# TCAN1146_PINOUT.net
KiCad netlist of a schematic drawn in Altium Designer
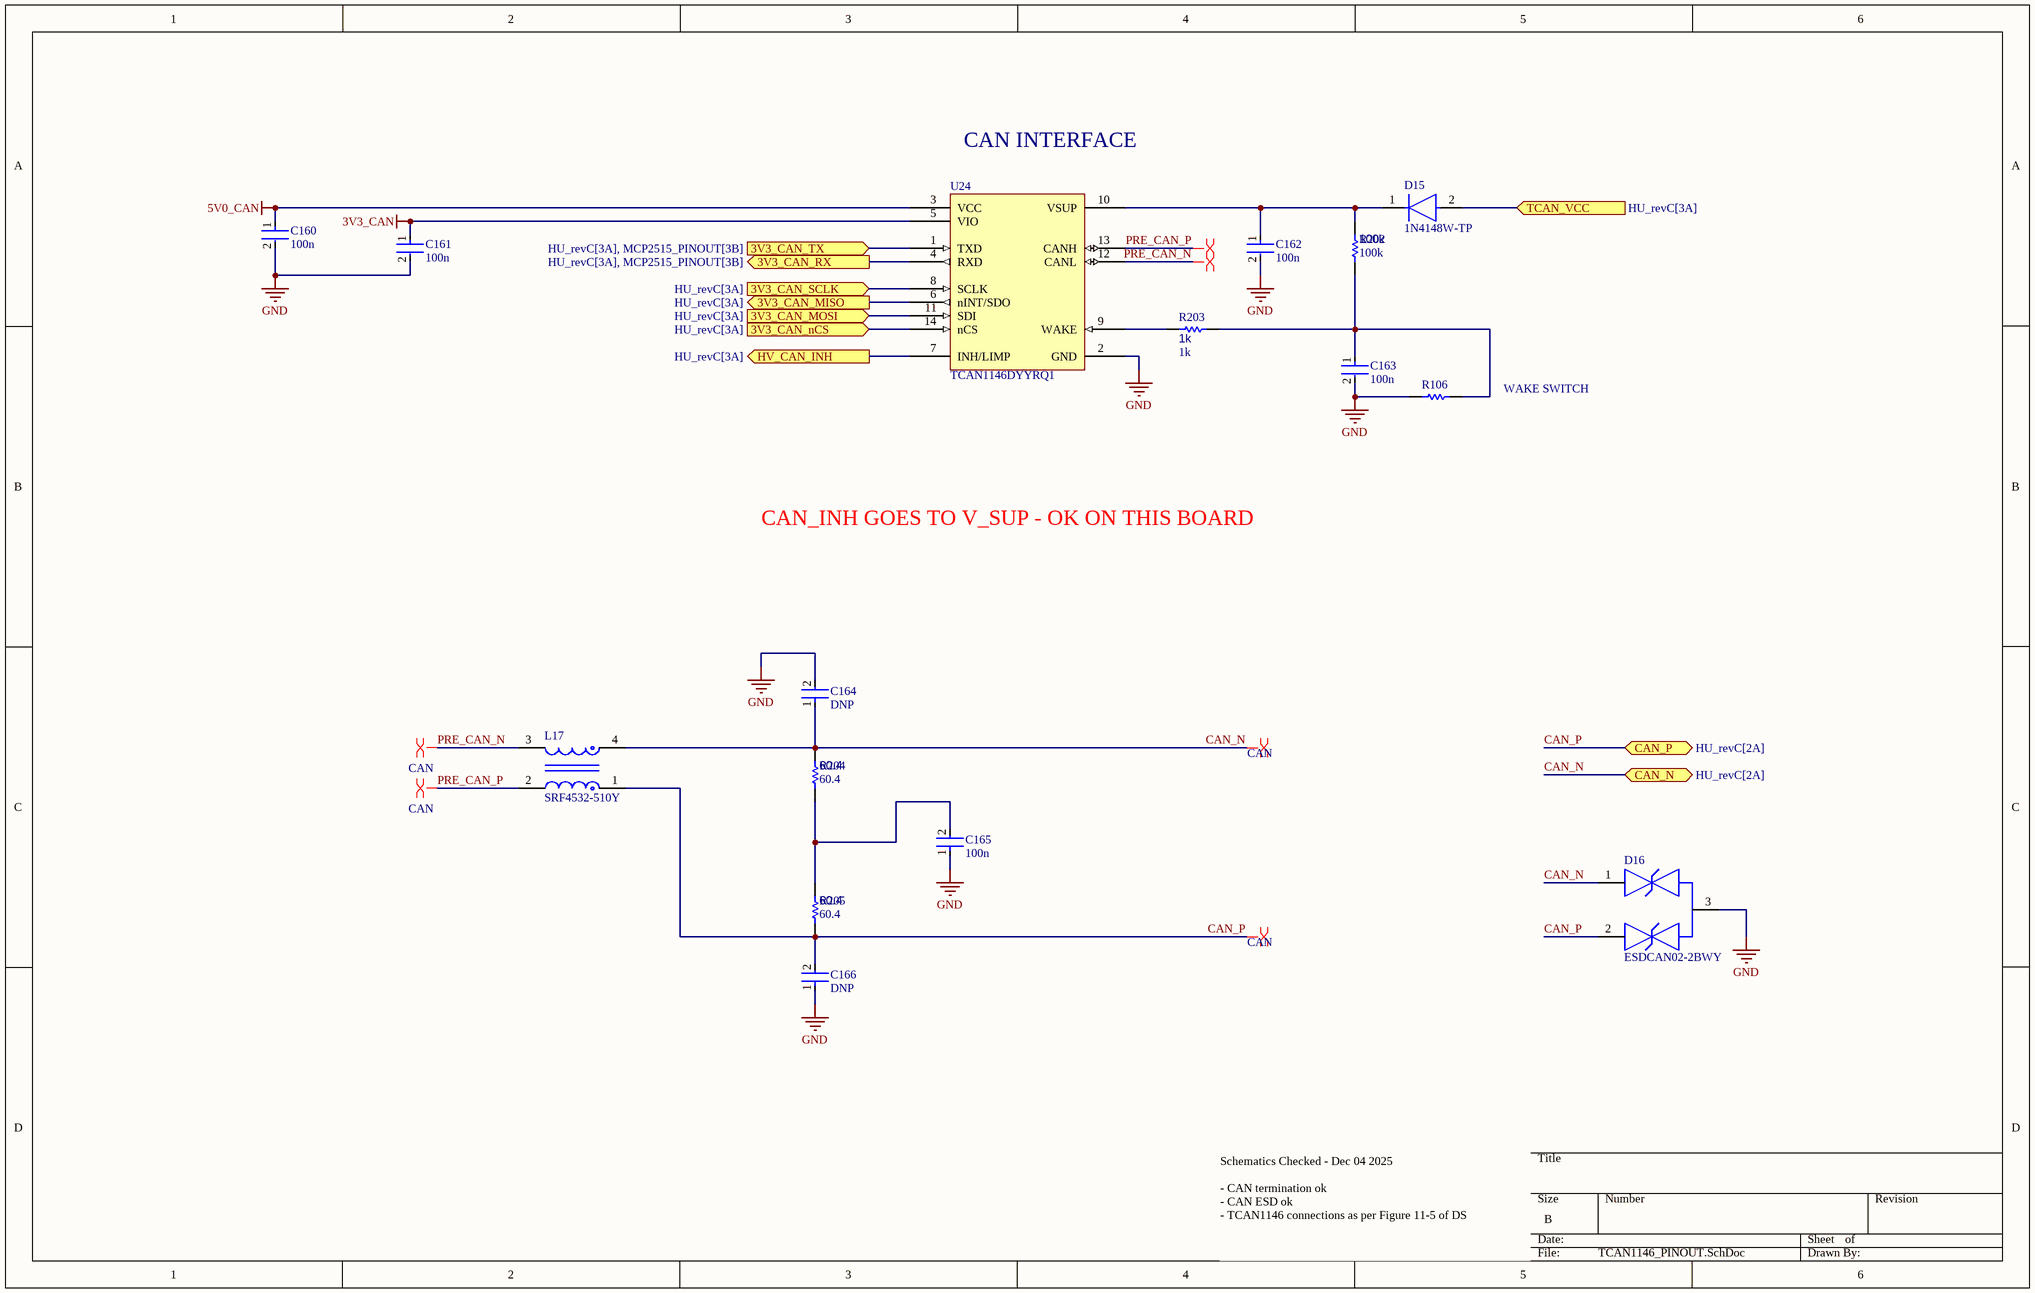
[diagram p0: TCAN1146_PINOUT.SchDoc]

(export (version "E")
  (design (tool "Eeschema 10.0.6"))
  (components
    (comp (ref "C160")
      (value "100n")
      (footprint "FP-0402-L_1_0_0_05-W_0_5-IPC_A")
      (description "LARGE PADS, 0402 CAP, CHANGE COMMENT TO MATCH REAL P/N")
      (libsource (lib "Space Concordia") (part "b4654b650e69147ec39a6b967a45e02"))
    )
    (comp (ref "C161")
      (value "100n")
      (footprint "FP-0402-L_1_0_0_05-W_0_5-IPC_A")
      (description "LARGE PADS, 0402 CAP, CHANGE COMMENT TO MATCH REAL P/N")
      (libsource (lib "Space Concordia") (part "b4654b650e69147ec39a6b967a45e02"))
    )
    (comp (ref "C162")
      (value "100n")
      (footprint "FP-0402-L_1_0_0_05-W_0_5-IPC_A")
      (description "LARGE PADS, 0402 CAP, CHANGE COMMENT TO MATCH REAL P/N")
      (libsource (lib "Space Concordia") (part "b4654b650e69147ec39a6b967a45e02"))
    )
    (comp (ref "C163")
      (value "100n")
      (footprint "FP-0402-L_1_0_0_05-W_0_5-IPC_A")
      (description "LARGE PADS, 0402 CAP, CHANGE COMMENT TO MATCH REAL P/N")
      (libsource (lib "Space Concordia") (part "b4654b650e69147ec39a6b967a45e02"))
    )
    (comp (ref "C164")
      (value "DNP")
      (footprint "FP-0402-L_1_0_0_05-W_0_5-IPC_A")
      (description "LARGE PADS, 0402 CAP, CHANGE COMMENT TO MATCH REAL P/N")
      (libsource (lib "Space Concordia") (part "b4654b650e69147ec39a6b967a45e02"))
    )
    (comp (ref "C165")
      (value "100n")
      (footprint "FP-0402-L_1_0_0_05-W_0_5-IPC_A")
      (description "LARGE PADS, 0402 CAP, CHANGE COMMENT TO MATCH REAL P/N")
      (libsource (lib "Space Concordia") (part "b4654b650e69147ec39a6b967a45e02"))
    )
    (comp (ref "C166")
      (value "DNP")
      (footprint "FP-0402-L_1_0_0_05-W_0_5-IPC_A")
      (description "LARGE PADS, 0402 CAP, CHANGE COMMENT TO MATCH REAL P/N")
      (libsource (lib "Space Concordia") (part "b4654b650e69147ec39a6b967a45e02"))
    )
    (comp (ref "D15")
      (value "1N4148W-TP")
      (footprint "FP-SOD-123-IPC_A")
      (description "DIODE GEN PURP 100V 150MA SOD123")
      (libsource (lib "Altium Content Vault") (part "d7152d700b627762746794eb795d46e"))
    )
    (comp (ref "D16")
      (value "ESDCAN02-2BWY")
      (footprint "FP-SOT323-3L-MFG")
      (description "TVS DIODE 26.5V 44V SOT323-3")
      (fields
        (field (name "MANUFACTURER") "STMicroelectronics")
        (field (name "OCTOPART") "https://octopart.com/esdcan02-2bwy-stmicroelectronics-58631133")
      )
      (libsource (lib "Altium Content Vault") (part "0b9019fb5e52ed66df21ec1535be59d"))
    )
    (comp (ref "L17")
      (value "SRF4532-510Y")
      (footprint "FP-SRF4532-MFG")
      (description "CMC 51UH 200MA 2LN 2KOHM SMD")
      (fields (field (name "TOLERANCE") "50%"))
      (libsource (lib "Altium Content Vault") (part "aca3f6a10b859f211cca95010157f3b"))
    )
    (comp (ref "R106")
      (value "0402 JUMPER")
      (footprint "RESC1005X40X25ML05T05")
      (description "READ THE NAME")
      (libsource (lib "Space Concordia") (part "CMP-009-00206-2"))
    )
    (comp (ref "R202")
      (value "100k")
      (footprint "R0603B")
      (description "Resistor")
      (fields (field (name "ALTIUM_VALUE") "100k"))
      (libsource (lib "Space Concordia") (part "Resistor"))
    )
    (comp (ref "R203")
      (value "1k")
      (footprint "R0603B")
      (description "Resistor")
      (fields (field (name "ALTIUM_VALUE") "1k"))
      (libsource (lib "Space Concordia") (part "Resistor"))
    )
    (comp (ref "R204")
      (value "60.4")
      (footprint "R0603B")
      (description "Resistor")
      (fields (field (name "ALTIUM_VALUE") "60.4"))
      (libsource (lib "Space Concordia") (part "Resistor"))
    )
    (comp (ref "R205")
      (value "60.4")
      (footprint "R0603B")
      (description "Resistor")
      (fields (field (name "ALTIUM_VALUE") "60.4"))
      (libsource (lib "Space Concordia") (part "Resistor"))
    )
    (comp (ref "U24")
      (value "TCAN1146DYYRQ1")
      (footprint "TCAN1146DYYRQ1-Footprint-1")
      (libsource (lib "Space Concordia") (part "CMP-015-00012-2"))
    )
  )
  (nets
    (net (code "1") (name "/3V3_CAN_MISO") (class "Default")
      (node (ref "U24") (pin "6") (pinfunction "nINT/SDO_6") (pintype "output"))
    )
    (net (code "2") (name "/3V3_CAN_MOSI") (class "Default")
      (node (ref "U24") (pin "11") (pinfunction "SDI_11") (pintype "input"))
    )
    (net (code "3") (name "/3V3_CAN_RX") (class "Default")
      (node (ref "U24") (pin "4") (pinfunction "RXD_4") (pintype "output"))
    )
    (net (code "4") (name "/3V3_CAN_SCLK") (class "Default")
      (node (ref "U24") (pin "8") (pinfunction "SCLK_8") (pintype "input"))
    )
    (net (code "5") (name "/3V3_CAN_TX") (class "Default")
      (node (ref "U24") (pin "1") (pinfunction "TXD_1") (pintype "input"))
    )
    (net (code "6") (name "/3V3_CAN_nCS") (class "Default")
      (node (ref "U24") (pin "14") (pinfunction "nCS_14") (pintype "input"))
    )
    (net (code "7") (name "/CAN_N") (class "Default")
      (node (ref "C164") (pin "1") (pinfunction "1_1") (pintype "passive"))
      (node (ref "D16") (pin "1") (pinfunction "1_1") (pintype "passive"))
      (node (ref "L17") (pin "4") (pinfunction "4_4") (pintype "passive"))
      (node (ref "R204") (pin "2") (pinfunction "2_2") (pintype "passive"))
    )
    (net (code "8") (name "/CAN_P") (class "Default")
      (node (ref "C166") (pin "2") (pinfunction "2_2") (pintype "passive"))
      (node (ref "D16") (pin "2") (pinfunction "2_2") (pintype "passive"))
      (node (ref "L17") (pin "1") (pinfunction "1_1") (pintype "passive"))
      (node (ref "R205") (pin "1") (pinfunction "1_1") (pintype "passive"))
    )
    (net (code "9") (name "/HV_CAN_INH") (class "Default")
      (node (ref "U24") (pin "7") (pinfunction "INH/LIMP_7") (pintype "passive"))
    )
    (net (code "10") (name "/PRE_CAN_N") (class "Default")
      (node (ref "L17") (pin "3") (pinfunction "3_3") (pintype "passive"))
      (node (ref "U24") (pin "12") (pinfunction "CANL_12") (pintype "bidirectional"))
    )
    (net (code "11") (name "/PRE_CAN_P") (class "Default")
      (node (ref "L17") (pin "2") (pinfunction "2_2") (pintype "passive"))
      (node (ref "U24") (pin "13") (pinfunction "CANH_13") (pintype "bidirectional"))
    )
    (net (code "12") (name "/TCAN_VCC") (class "Default")
      (node (ref "D15") (pin "2") (pinfunction "A_2") (pintype "passive"))
    )
    (net (code "13") (name "3V3_CAN") (class "Default")
      (node (ref "C161") (pin "1") (pinfunction "1_1") (pintype "passive"))
      (node (ref "U24") (pin "5") (pinfunction "VIO_5") (pintype "power_in"))
    )
    (net (code "14") (name "5V0_CAN") (class "Default")
      (node (ref "C160") (pin "1") (pinfunction "1_1") (pintype "passive"))
      (node (ref "U24") (pin "3") (pinfunction "VCC_3") (pintype "power_in"))
    )
    (net (code "15") (name "GND") (class "Default")
      (node (ref "C160") (pin "2") (pinfunction "2_2") (pintype "passive"))
      (node (ref "C161") (pin "2") (pinfunction "2_2") (pintype "passive"))
      (node (ref "C162") (pin "2") (pinfunction "2_2") (pintype "passive"))
      (node (ref "C163") (pin "2") (pinfunction "2_2") (pintype "passive"))
      (node (ref "C164") (pin "2") (pinfunction "2_2") (pintype "passive"))
      (node (ref "C165") (pin "1") (pinfunction "1_1") (pintype "passive"))
      (node (ref "C166") (pin "1") (pinfunction "1_1") (pintype "passive"))
      (node (ref "D16") (pin "3") (pinfunction "3_3") (pintype "passive"))
      (node (ref "R106") (pin "1") (pinfunction "1_1") (pintype "passive"))
      (node (ref "U24") (pin "2") (pinfunction "GND_2") (pintype "power_in"))
    )
    (net (code "16") (name "Net-(C163-Pad1)") (class "Default")
      (node (ref "C163") (pin "1") (pinfunction "1_1") (pintype "passive"))
      (node (ref "R106") (pin "2") (pinfunction "2_2") (pintype "passive"))
      (node (ref "R202") (pin "1") (pinfunction "1_1") (pintype "passive"))
      (node (ref "R203") (pin "2") (pinfunction "2_2") (pintype "passive"))
    )
    (net (code "17") (name "Net-(C165-Pad2)") (class "Default")
      (node (ref "C165") (pin "2") (pinfunction "2_2") (pintype "passive"))
      (node (ref "R204") (pin "1") (pinfunction "1_1") (pintype "passive"))
      (node (ref "R205") (pin "2") (pinfunction "2_2") (pintype "passive"))
    )
    (net (code "18") (name "Net-(D15-C)") (class "Default")
      (node (ref "C162") (pin "1") (pinfunction "1_1") (pintype "passive"))
      (node (ref "D15") (pin "1") (pinfunction "C_1") (pintype "passive"))
      (node (ref "R202") (pin "2") (pinfunction "2_2") (pintype "passive"))
      (node (ref "U24") (pin "10") (pinfunction "VSUP_10") (pintype "power_in"))
    )
    (net (code "19") (name "Net-(U24-WAKE)") (class "Default")
      (node (ref "R203") (pin "1") (pinfunction "1_1") (pintype "passive"))
      (node (ref "U24") (pin "9") (pinfunction "WAKE_9") (pintype "input"))
    )
  )
)
